# Main.net
KiCad netlist of a schematic drawn in Altium Designer
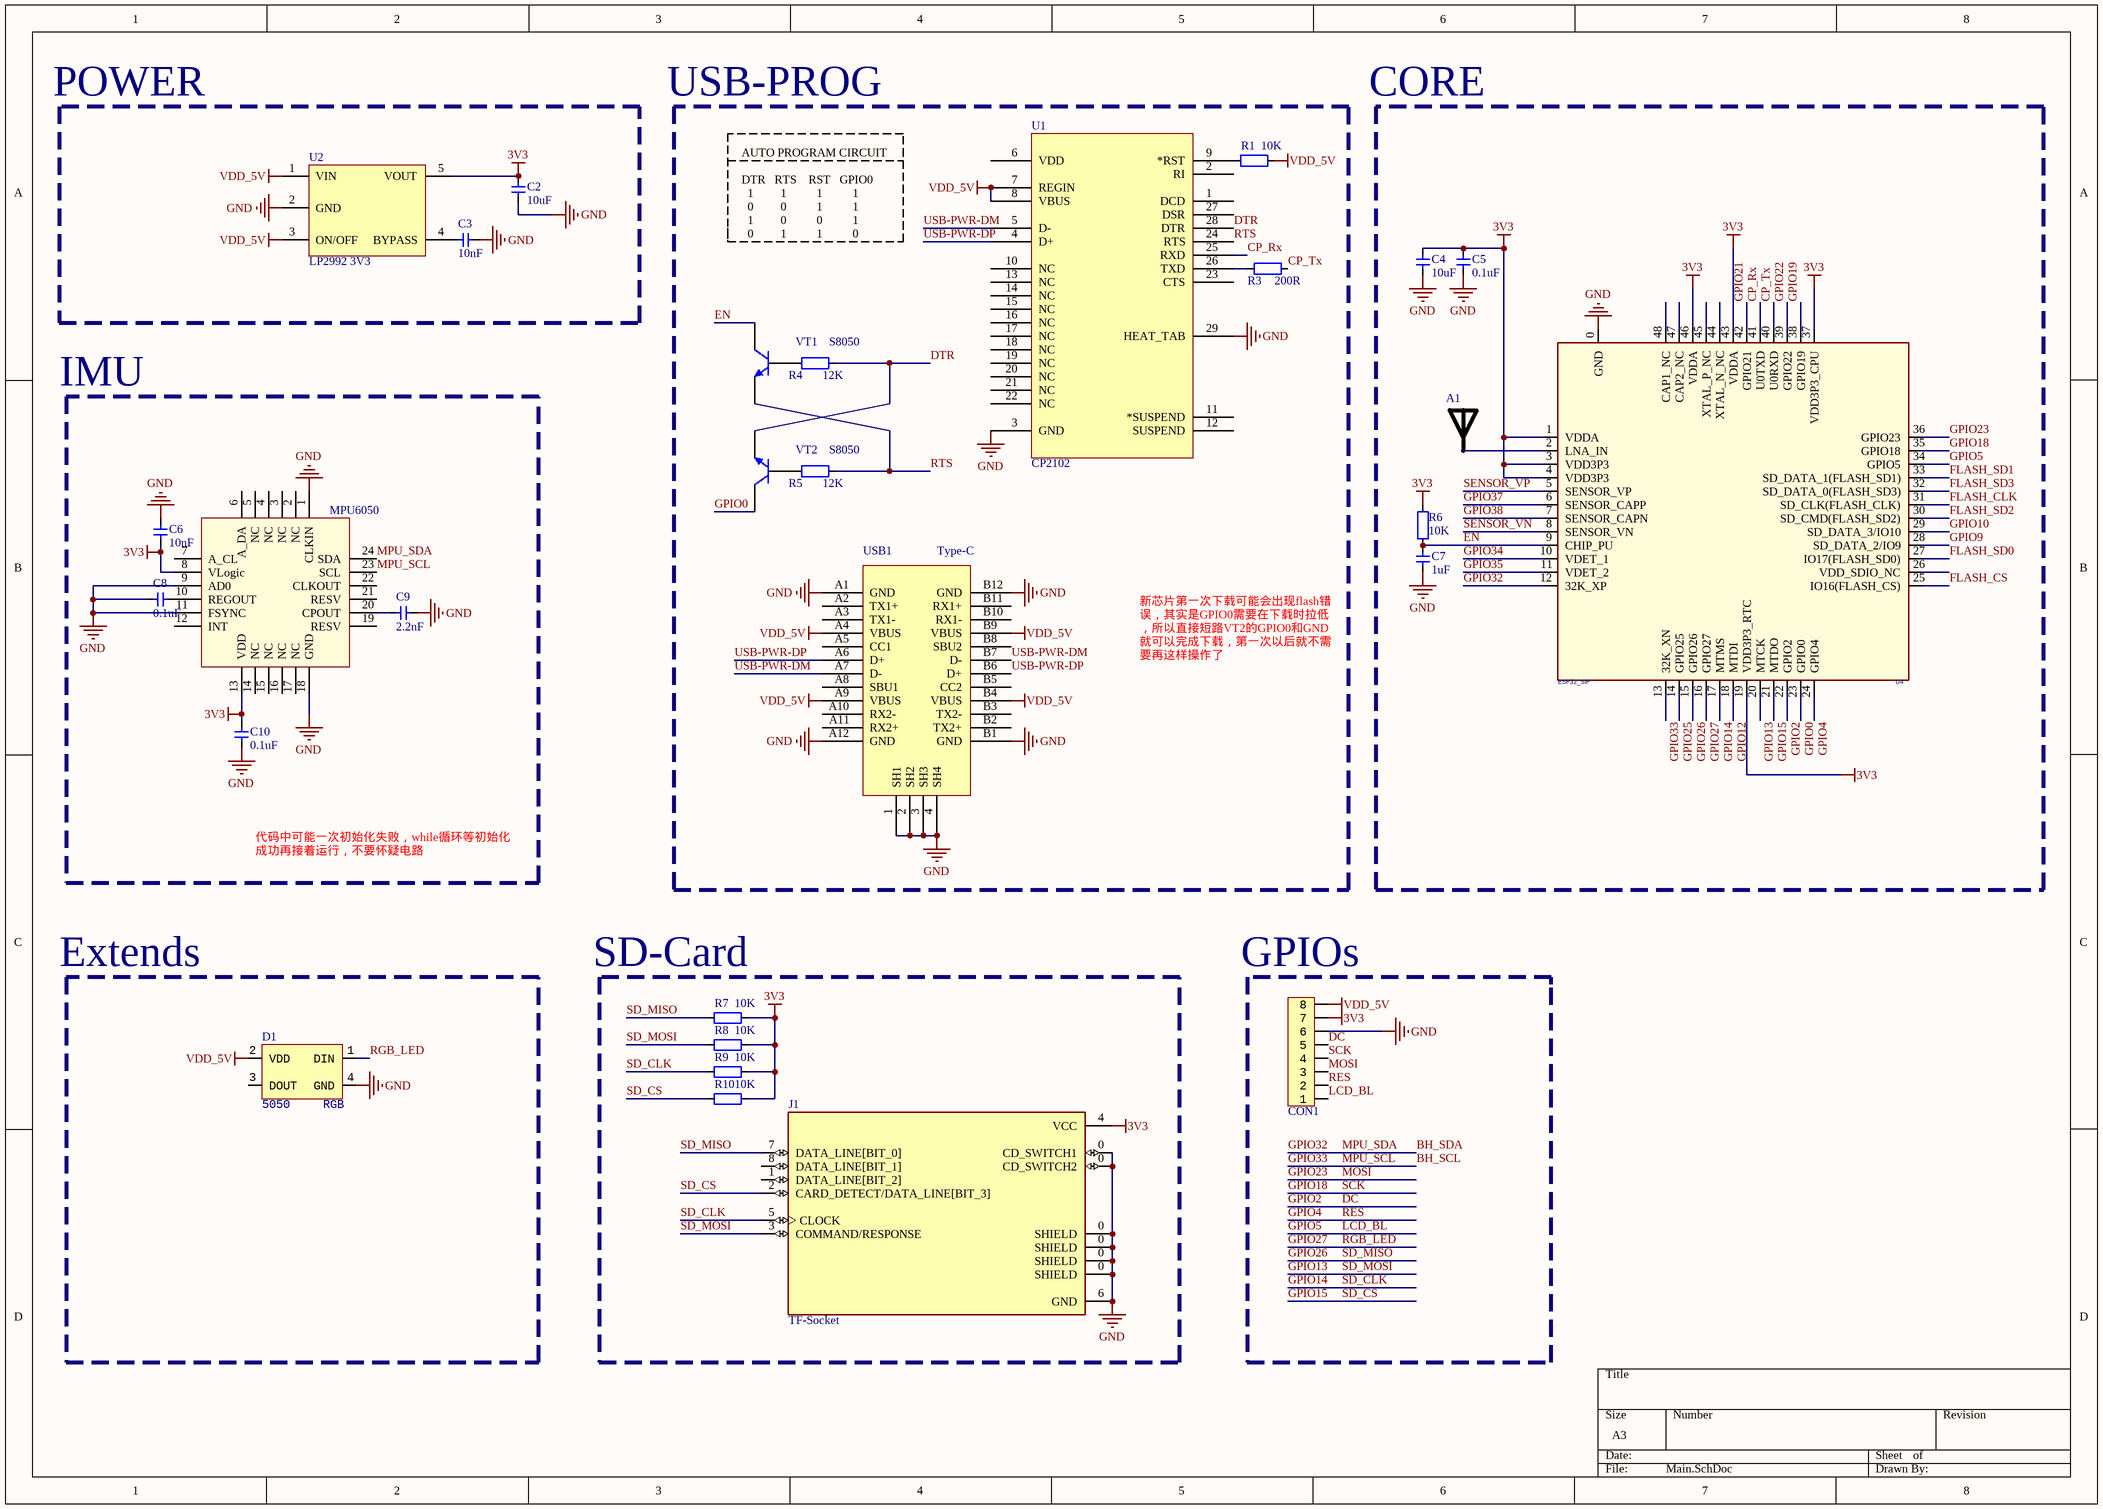
[diagram p0: Main.SchDoc]

(export (version "E")
  (design (tool "Eeschema 10.0.6"))
  (components
    (comp (ref "A1")
      (value "RAINSUN")
      (footprint "ANT-Rainsun-AN5120")
      (libsource (lib "MyPcbLib") (part "ANT-Rainsun-AP5120"))
    )
    (comp (ref "C2")
      (value "10uF")
      (footprint "CAP_0402")
      (description "Capacitor")
      (libsource (lib "MyPcbLib") (part "电容-0402"))
    )
    (comp (ref "C3")
      (value "10nF")
      (footprint "CAP_0402")
      (description "Capacitor")
      (libsource (lib "MyPcbLib") (part "电容-0402"))
    )
    (comp (ref "C4")
      (value "10uF")
      (footprint "CAP_0402")
      (description "Capacitor")
      (libsource (lib "MyPcbLib") (part "电容-0402"))
    )
    (comp (ref "C5")
      (value "0.1uF")
      (footprint "CAP_0402")
      (description "Capacitor")
      (libsource (lib "MyPcbLib") (part "电容-0402"))
    )
    (comp (ref "C6")
      (value "10nF")
      (footprint "CAP_0402")
      (description "Capacitor")
      (libsource (lib "MyPcbLib") (part "电容-0402"))
    )
    (comp (ref "C7")
      (value "1uF")
      (footprint "CAP_0402")
      (description "Capacitor")
      (libsource (lib "MyPcbLib") (part "电容-0402"))
    )
    (comp (ref "C8")
      (value "0.1uF")
      (footprint "CAP_0402")
      (description "Capacitor")
      (libsource (lib "MyPcbLib") (part "电容-0402"))
    )
    (comp (ref "C9")
      (value "2.2nF")
      (footprint "CAP_0402")
      (description "Capacitor")
      (libsource (lib "MyPcbLib") (part "电容-0402"))
    )
    (comp (ref "C10")
      (value "0.1uF")
      (footprint "CAP_0402")
      (description "Capacitor")
      (libsource (lib "MyPcbLib") (part "电容-0402"))
    )
    (comp (ref "CON1")
      (value "FFC_0.5_8")
      (footprint "FFC_0.5_8")
      (description "FFC")
      (libsource (lib "KitSprout") (part "FFC_0.5_8"))
    )
    (comp (ref "D1")
      (value "RGB")
      (footprint "LED_WS2812_CE")
      (description "LED")
      (fields (field (name "TYPE") "5050"))
      (libsource (lib "KitSprout") (part "LED_5050_WS2812B"))
    )
    (comp (ref "J1")
      (value "TF-Socket")
      (footprint "TF_F")
      (description "10 _8 + 2_ Position Card Connector Secure Digital - microSDâ„¢ Surface Mount, Right Angle Gold")
      (fields (field (name "MP") "1140084168") (field (name "MF") "Amphenol Commercial Products"))
      (libsource (lib "MyPcbLib") (part "TF-Socket"))
    )
    (comp (ref "R1")
      (value "10K")
      (footprint "RES_0402")
      (description "Resistor")
      (libsource (lib "MyPcbLib") (part "电阻-0402"))
    )
    (comp (ref "R3")
      (value "200R")
      (footprint "RES_0402")
      (description "Resistor")
      (libsource (lib "MyPcbLib") (part "电阻-0402"))
    )
    (comp (ref "R4")
      (value "12K")
      (footprint "RES_0402")
      (description "Resistor")
      (libsource (lib "MyPcbLib") (part "电阻-0402"))
    )
    (comp (ref "R5")
      (value "12K")
      (footprint "RES_0402")
      (description "Resistor")
      (libsource (lib "MyPcbLib") (part "电阻-0402"))
    )
    (comp (ref "R6")
      (value "10K")
      (footprint "RES_0402")
      (description "Resistor")
      (libsource (lib "") (part "电阻-0402_1"))
    )
    (comp (ref "R7")
      (value "10K")
      (footprint "RES_0402")
      (description "Resistor")
      (libsource (lib "MyPcbLib") (part "电阻-0402"))
    )
    (comp (ref "R8")
      (value "10K")
      (footprint "RES_0402")
      (description "Resistor")
      (libsource (lib "MyPcbLib") (part "电阻-0402"))
    )
    (comp (ref "R9")
      (value "10K")
      (footprint "RES_0402")
      (description "Resistor")
      (libsource (lib "MyPcbLib") (part "电阻-0402"))
    )
    (comp (ref "R10")
      (value "10K")
      (footprint "RES_0402")
      (description "Resistor")
      (libsource (lib "MyPcbLib") (part "电阻-0402"))
    )
    (comp (ref "U1")
      (value "CP2102")
      (footprint "QFN-28")
      (description "USB转TTL")
      (libsource (lib "mLib") (part "CP2102"))
    )
    (comp (ref "U2")
      (value "LP2992 3V3")
      (footprint "SOT23-5")
      (description "LDO")
      (libsource (lib "MyPcbLib") (part "LP2992"))
    )
    (comp (ref "U3")
      (value "MPU6050")
      (footprint "QFN-24")
      (description "六轴传感器")
      (libsource (lib "mLib") (part "MPU6050"))
    )
    (comp (ref "U4")
      (value "ESP32_SIP")
      (footprint "QFN-48_7X7")
      (libsource (lib "MyPcbLib") (part "ESP32-PICO"))
    )
    (comp (ref "USB1")
      (value "Type-C")
      (footprint "Type-C-TOP")
      (libsource (lib "MyPcbLib") (part "USB-Type-C-TOP"))
    )
    (comp (ref "VT1")
      (value "S8050")
      (footprint "SMT_TRIODE_NPN")
      (description "Surface mount NPN transistor, package SOT-23")
      (libsource (lib "MyPcbLib") (part "SMT_TRIODE_NPN"))
    )
    (comp (ref "VT2")
      (value "S8050")
      (footprint "SMT_TRIODE_NPN")
      (description "Surface mount NPN transistor, package SOT-23")
      (libsource (lib "MyPcbLib") (part "SMT_TRIODE_NPN"))
    )
  )
  (nets
    (net (code "1") (name "/BH_SCL") (class "Default")
      (node (ref "U3") (pin "23") (pinfunction "SCL_23") (pintype "passive"))
      (node (ref "U4") (pin "13") (pinfunction "32K_XN_13") (pintype "passive"))
    )
    (net (code "2") (name "/BH_SDA") (class "Default")
      (node (ref "U3") (pin "24") (pinfunction "SDA_24") (pintype "passive"))
      (node (ref "U4") (pin "12") (pinfunction "32K_XP_12") (pintype "passive"))
    )
    (net (code "3") (name "/CP_Rx") (class "Default")
      (node (ref "U1") (pin "25") (pinfunction "RXD_25") (pintype "passive"))
      (node (ref "U4") (pin "41") (pinfunction "U0TXD_41") (pintype "power_in"))
    )
    (net (code "4") (name "/CP_Tx") (class "Default")
      (node (ref "R3") (pin "1") (pinfunction "1_1") (pintype "passive"))
      (node (ref "U4") (pin "40") (pinfunction "U0RXD_40") (pintype "power_in"))
    )
    (net (code "5") (name "/DC") (class "Default")
      (node (ref "CON1") (pin "5") (pinfunction "5_5") (pintype "passive"))
      (node (ref "U4") (pin "22") (pinfunction "GPIO2_22") (pintype "passive"))
    )
    (net (code "6") (name "/DTR") (class "Default")
      (node (ref "R4") (pin "1") (pinfunction "1_1") (pintype "passive"))
      (node (ref "U1") (pin "28") (pinfunction "DTR_28") (pintype "passive"))
      (node (ref "VT2") (pin "2") (pinfunction "E_2") (pintype "passive"))
    )
    (net (code "7") (name "/EN") (class "Default")
      (node (ref "C7") (pin "1") (pinfunction "1_1") (pintype "passive"))
      (node (ref "R6") (pin "2") (pinfunction "2_2") (pintype "passive"))
      (node (ref "U4") (pin "9") (pinfunction "CHIP_PU_9") (pintype "passive"))
      (node (ref "VT1") (pin "3") (pinfunction "C_3") (pintype "passive"))
    )
    (net (code "8") (name "/FLASH_CLK") (class "Default")
      (node (ref "U4") (pin "31") (pinfunction "SD_CLK(FLASH_CLK)_31") (pintype "passive"))
    )
    (net (code "9") (name "/FLASH_CS") (class "Default")
      (node (ref "U4") (pin "25") (pinfunction "IO16(FLASH_CS)_25") (pintype "passive"))
    )
    (net (code "10") (name "/FLASH_SD0") (class "Default")
      (node (ref "U4") (pin "27") (pinfunction "IO17(FLASH_SD0)_27") (pintype "passive"))
    )
    (net (code "11") (name "/FLASH_SD1") (class "Default")
      (node (ref "U4") (pin "33") (pinfunction "SD_DATA_1(FLASH_SD1)_33") (pintype "passive"))
    )
    (net (code "12") (name "/FLASH_SD2") (class "Default")
      (node (ref "U4") (pin "30") (pinfunction "SD_CMD(FLASH_SD2)_30") (pintype "passive"))
    )
    (net (code "13") (name "/FLASH_SD3") (class "Default")
      (node (ref "U4") (pin "32") (pinfunction "SD_DATA_0(FLASH_SD3)_32") (pintype "passive"))
    )
    (net (code "14") (name "/GPIO0") (class "Default")
      (node (ref "U4") (pin "23") (pinfunction "GPIO0_23") (pintype "passive"))
      (node (ref "VT2") (pin "3") (pinfunction "C_3") (pintype "passive"))
    )
    (net (code "15") (name "/GPIO4") (class "Default")
      (node (ref "CON1") (pin "2") (pinfunction "2_2") (pintype "passive"))
      (node (ref "U4") (pin "24") (pinfunction "GPIO4_24") (pintype "passive"))
    )
    (net (code "16") (name "/GPIO5") (class "Default")
      (node (ref "CON1") (pin "1") (pinfunction "1_1") (pintype "passive"))
      (node (ref "U4") (pin "34") (pinfunction "GPIO5_34") (pintype "passive"))
    )
    (net (code "17") (name "/GPIO9") (class "Default")
      (node (ref "U4") (pin "28") (pinfunction "SD_DATA_2/IO9_28") (pintype "passive"))
    )
    (net (code "18") (name "/GPIO10") (class "Default")
      (node (ref "U4") (pin "29") (pinfunction "SD_DATA_3/IO10_29") (pintype "passive"))
    )
    (net (code "19") (name "/GPIO12") (class "Default")
      (node (ref "U4") (pin "18") (pinfunction "MTDI_18") (pintype "passive"))
    )
    (net (code "20") (name "/GPIO13") (class "Default")
      (node (ref "J1") (pin "3") (pinfunction "COMMAND/RESPONSE_3") (pintype "bidirectional"))
      (node (ref "R8") (pin "2") (pinfunction "2_2") (pintype "passive"))
      (node (ref "U4") (pin "20") (pinfunction "MTCK_20") (pintype "passive"))
    )
    (net (code "21") (name "/GPIO14") (class "Default")
      (node (ref "J1") (pin "5") (pinfunction "CLOCK_5") (pintype "bidirectional"))
      (node (ref "R9") (pin "2") (pinfunction "2_2") (pintype "passive"))
      (node (ref "U4") (pin "17") (pinfunction "MTMS_17") (pintype "passive"))
    )
    (net (code "22") (name "/GPIO15") (class "Default")
      (node (ref "J1") (pin "2") (pinfunction "CARD_DETECT/DATA_LINE[BIT_3]_2") (pintype "bidirectional"))
      (node (ref "R10") (pin "2") (pinfunction "2_2") (pintype "passive"))
      (node (ref "U4") (pin "21") (pinfunction "MTDO_21") (pintype "passive"))
    )
    (net (code "23") (name "/GPIO18") (class "Default")
      (node (ref "CON1") (pin "4") (pinfunction "4_4") (pintype "passive"))
      (node (ref "U4") (pin "35") (pinfunction "GPIO18_35") (pintype "passive"))
    )
    (net (code "24") (name "/GPIO19") (class "Default")
      (node (ref "U4") (pin "38") (pinfunction "GPIO19_38") (pintype "passive"))
    )
    (net (code "25") (name "/GPIO21") (class "Default")
      (node (ref "U4") (pin "42") (pinfunction "GPIO21_42") (pintype "passive"))
    )
    (net (code "26") (name "/GPIO22") (class "Default")
      (node (ref "U4") (pin "39") (pinfunction "GPIO22_39") (pintype "passive"))
    )
    (net (code "27") (name "/GPIO23") (class "Default")
      (node (ref "CON1") (pin "3") (pinfunction "3_3") (pintype "passive"))
      (node (ref "U4") (pin "36") (pinfunction "GPIO23_36") (pintype "passive"))
    )
    (net (code "28") (name "/GPIO25") (class "Default")
      (node (ref "U4") (pin "14") (pinfunction "GPIO25_14") (pintype "passive"))
    )
    (net (code "29") (name "/GPIO26") (class "Default")
      (node (ref "J1") (pin "7") (pinfunction "DATA_LINE[BIT_0]_7") (pintype "bidirectional"))
      (node (ref "R7") (pin "2") (pinfunction "2_2") (pintype "passive"))
      (node (ref "U4") (pin "15") (pinfunction "GPIO26_15") (pintype "passive"))
    )
    (net (code "30") (name "/GPIO27") (class "Default")
      (node (ref "D1") (pin "1") (pinfunction "DIN_1") (pintype "passive"))
      (node (ref "U4") (pin "16") (pinfunction "GPIO27_16") (pintype "passive"))
    )
    (net (code "31") (name "/GPIO34") (class "Default")
      (node (ref "U4") (pin "10") (pinfunction "VDET_1_10") (pintype "passive"))
    )
    (net (code "32") (name "/GPIO35") (class "Default")
      (node (ref "U4") (pin "11") (pinfunction "VDET_2_11") (pintype "passive"))
    )
    (net (code "33") (name "/GPIO37") (class "Default")
      (node (ref "U4") (pin "6") (pinfunction "SENSOR_CAPP_6") (pintype "passive"))
    )
    (net (code "34") (name "/GPIO38") (class "Default")
      (node (ref "U4") (pin "7") (pinfunction "SENSOR_CAPN_7") (pintype "passive"))
    )
    (net (code "35") (name "/RTS") (class "Default")
      (node (ref "R5") (pin "1") (pinfunction "1_1") (pintype "passive"))
      (node (ref "U1") (pin "24") (pinfunction "RTS_24") (pintype "passive"))
      (node (ref "VT1") (pin "2") (pinfunction "E_2") (pintype "passive"))
    )
    (net (code "36") (name "/SENSOR_VN") (class "Default")
      (node (ref "U4") (pin "8") (pinfunction "SENSOR_VN_8") (pintype "passive"))
    )
    (net (code "37") (name "/SENSOR_VP") (class "Default")
      (node (ref "U4") (pin "5") (pinfunction "SENSOR_VP_5") (pintype "passive"))
    )
    (net (code "38") (name "/USB-PWR-DM") (class "Default")
      (node (ref "U1") (pin "5") (pinfunction "D-_5") (pintype "passive"))
      (node (ref "USB1") (pin "A7") (pinfunction "D-_A7") (pintype "passive"))
      (node (ref "USB1") (pin "B7") (pinfunction "D-_B7") (pintype "passive"))
    )
    (net (code "39") (name "/USB-PWR-DP") (class "Default")
      (node (ref "U1") (pin "4") (pinfunction "D+_4") (pintype "passive"))
      (node (ref "USB1") (pin "A6") (pinfunction "D+_A6") (pintype "passive"))
      (node (ref "USB1") (pin "B6") (pinfunction "D+_B6") (pintype "passive"))
    )
    (net (code "40") (name "3V3") (class "Default")
      (node (ref "C10") (pin "2") (pinfunction "2_2") (pintype "passive"))
      (node (ref "C2") (pin "2") (pinfunction "2_2") (pintype "passive"))
      (node (ref "C4") (pin "2") (pinfunction "2_2") (pintype "passive"))
      (node (ref "C5") (pin "2") (pinfunction "2_2") (pintype "passive"))
      (node (ref "C6") (pin "1") (pinfunction "1_1") (pintype "passive"))
      (node (ref "CON1") (pin "7") (pinfunction "7_7") (pintype "passive"))
      (node (ref "J1") (pin "4") (pinfunction "VCC_4") (pintype "power_in"))
      (node (ref "R10") (pin "1") (pinfunction "1_1") (pintype "passive"))
      (node (ref "R6") (pin "1") (pinfunction "1_1") (pintype "passive"))
      (node (ref "R7") (pin "1") (pinfunction "1_1") (pintype "passive"))
      (node (ref "R8") (pin "1") (pinfunction "1_1") (pintype "passive"))
      (node (ref "R9") (pin "1") (pinfunction "1_1") (pintype "passive"))
      (node (ref "U2") (pin "5") (pinfunction "VOUT_5") (pintype "passive"))
      (node (ref "U3") (pin "13") (pinfunction "VDD_13") (pintype "passive"))
      (node (ref "U3") (pin "8") (pinfunction "VLogic_8") (pintype "passive"))
      (node (ref "U4") (pin "1") (pinfunction "VDDA_1") (pintype "power_in"))
      (node (ref "U4") (pin "19") (pinfunction "VDD3P3_RTC_19") (pintype "power_in"))
      (node (ref "U4") (pin "3") (pinfunction "VDD3P3_3") (pintype "power_in"))
      (node (ref "U4") (pin "37") (pinfunction "VDD3P3_CPU_37") (pintype "power_in"))
      (node (ref "U4") (pin "4") (pinfunction "VDD3P3_4") (pintype "power_in"))
      (node (ref "U4") (pin "43") (pinfunction "VDDA_43") (pintype "power_in"))
      (node (ref "U4") (pin "46") (pinfunction "VDDA_46") (pintype "power_in"))
    )
    (net (code "41") (name "GND") (class "Default")
      (node (ref "C10") (pin "1") (pinfunction "1_1") (pintype "passive"))
      (node (ref "C2") (pin "1") (pinfunction "1_1") (pintype "passive"))
      (node (ref "C3") (pin "1") (pinfunction "1_1") (pintype "passive"))
      (node (ref "C4") (pin "1") (pinfunction "1_1") (pintype "passive"))
      (node (ref "C5") (pin "1") (pinfunction "1_1") (pintype "passive"))
      (node (ref "C6") (pin "2") (pinfunction "2_2") (pintype "passive"))
      (node (ref "C7") (pin "2") (pinfunction "2_2") (pintype "passive"))
      (node (ref "C8") (pin "2") (pinfunction "2_2") (pintype "passive"))
      (node (ref "C9") (pin "1") (pinfunction "1_1") (pintype "passive"))
      (node (ref "CON1") (pin "6") (pinfunction "6_6") (pintype "passive"))
      (node (ref "D1") (pin "4") (pinfunction "GND_4") (pintype "passive"))
      (node (ref "J1") (pin "0") (pinfunction "SHIELD_0") (pintype "passive"))
      (node (ref "J1") (pin "6") (pinfunction "GND_6") (pintype "power_in"))
      (node (ref "U1") (pin "29") (pinfunction "HEAT_TAB_29") (pintype "passive"))
      (node (ref "U1") (pin "3") (pinfunction "GND_3") (pintype "passive"))
      (node (ref "U2") (pin "2") (pinfunction "GND_2") (pintype "passive"))
      (node (ref "U3") (pin "1") (pinfunction "CLKIN_1") (pintype "passive"))
      (node (ref "U3") (pin "11") (pinfunction "FSYNC_11") (pintype "passive"))
      (node (ref "U3") (pin "18") (pinfunction "GND_18") (pintype "passive"))
      (node (ref "U3") (pin "9") (pinfunction "AD0_9") (pintype "passive"))
      (node (ref "U4") (pin "0") (pinfunction "GND_0") (pintype "power_in"))
      (node (ref "USB1") (pin "1") (pinfunction "SH1_1") (pintype "passive"))
      (node (ref "USB1") (pin "2") (pinfunction "SH2_2") (pintype "passive"))
      (node (ref "USB1") (pin "3") (pinfunction "SH3_3") (pintype "passive"))
      (node (ref "USB1") (pin "4") (pinfunction "SH4_4") (pintype "passive"))
      (node (ref "USB1") (pin "A1") (pinfunction "GND_A1") (pintype "passive"))
      (node (ref "USB1") (pin "A12") (pinfunction "GND_A12") (pintype "passive"))
      (node (ref "USB1") (pin "B1") (pinfunction "GND_B1") (pintype "passive"))
      (node (ref "USB1") (pin "B12") (pinfunction "GND_B12") (pintype "passive"))
    )
    (net (code "42") (name "Net-(U1-*RST)") (class "Default")
      (node (ref "R1") (pin "2") (pinfunction "2_2") (pintype "passive"))
      (node (ref "U1") (pin "9") (pinfunction "*RST_9") (pintype "passive"))
    )
    (net (code "43") (name "Net-(U1-TXD)") (class "Default")
      (node (ref "R3") (pin "2") (pinfunction "2_2") (pintype "passive"))
      (node (ref "U1") (pin "26") (pinfunction "TXD_26") (pintype "passive"))
    )
    (net (code "44") (name "Net-(U2-BYPASS)") (class "Default")
      (node (ref "C3") (pin "2") (pinfunction "2_2") (pintype "passive"))
      (node (ref "U2") (pin "4") (pinfunction "BYPASS_4") (pintype "passive"))
    )
    (net (code "45") (name "Net-(U3-CPOUT)") (class "Default")
      (node (ref "C9") (pin "2") (pinfunction "2_2") (pintype "passive"))
      (node (ref "U3") (pin "20") (pinfunction "CPOUT_20") (pintype "passive"))
    )
    (net (code "46") (name "Net-(U3-REGOUT)") (class "Default")
      (node (ref "C8") (pin "1") (pinfunction "1_1") (pintype "passive"))
      (node (ref "U3") (pin "10") (pinfunction "REGOUT_10") (pintype "passive"))
    )
    (net (code "47") (name "Net-(U4-LNA_IN)") (class "Default")
      (node (ref "A1") (pin "1") (pinfunction "1_1") (pintype "passive"))
      (node (ref "U4") (pin "2") (pinfunction "LNA_IN_2") (pintype "passive"))
    )
    (net (code "48") (name "Net-(VT1-B)") (class "Default")
      (node (ref "R4") (pin "2") (pinfunction "2_2") (pintype "passive"))
      (node (ref "VT1") (pin "1") (pinfunction "B_1") (pintype "passive"))
    )
    (net (code "49") (name "Net-(VT2-B)") (class "Default")
      (node (ref "R5") (pin "2") (pinfunction "2_2") (pintype "passive"))
      (node (ref "VT2") (pin "1") (pinfunction "B_1") (pintype "passive"))
    )
    (net (code "50") (name "VDD_5V") (class "Default")
      (node (ref "CON1") (pin "8") (pinfunction "8_8") (pintype "passive"))
      (node (ref "D1") (pin "2") (pinfunction "VDD_2") (pintype "passive"))
      (node (ref "R1") (pin "1") (pinfunction "1_1") (pintype "passive"))
      (node (ref "U1") (pin "7") (pinfunction "REGIN_7") (pintype "passive"))
      (node (ref "U1") (pin "8") (pinfunction "VBUS_8") (pintype "passive"))
      (node (ref "U2") (pin "1") (pinfunction "VIN_1") (pintype "passive"))
      (node (ref "U2") (pin "3") (pinfunction "ON/OFF_3") (pintype "passive"))
      (node (ref "USB1") (pin "A4") (pinfunction "VBUS_A4") (pintype "passive"))
      (node (ref "USB1") (pin "A9") (pinfunction "VBUS_A9") (pintype "passive"))
      (node (ref "USB1") (pin "B4") (pinfunction "VBUS_B4") (pintype "passive"))
      (node (ref "USB1") (pin "B9") (pinfunction "VBUS_B9") (pintype "passive"))
    )
    (net (code "51") (name "unconnected-(D1-DOUT-Pad3)") (class "Default")
      (node (ref "D1") (pin "3") (pinfunction "DOUT_3") (pintype "passive"))
    )
    (net (code "52") (name "unconnected-(J1-DATA_LINE[BIT_1]-Pad8)") (class "Default")
      (node (ref "J1") (pin "8") (pinfunction "DATA_LINE[BIT_1]_8") (pintype "bidirectional"))
    )
    (net (code "53") (name "unconnected-(J1-DATA_LINE[BIT_2]-Pad1)") (class "Default")
      (node (ref "J1") (pin "1") (pinfunction "DATA_LINE[BIT_2]_1") (pintype "bidirectional"))
    )
    (net (code "54") (name "unconnected-(U1-*SUSPEND-Pad11)") (class "Default")
      (node (ref "U1") (pin "11") (pinfunction "*SUSPEND_11") (pintype "passive"))
    )
    (net (code "55") (name "unconnected-(U1-CTS-Pad23)") (class "Default")
      (node (ref "U1") (pin "23") (pinfunction "CTS_23") (pintype "passive"))
    )
    (net (code "56") (name "unconnected-(U1-DCD-Pad1)") (class "Default")
      (node (ref "U1") (pin "1") (pinfunction "DCD_1") (pintype "passive"))
    )
    (net (code "57") (name "unconnected-(U1-DSR-Pad27)") (class "Default")
      (node (ref "U1") (pin "27") (pinfunction "DSR_27") (pintype "passive"))
    )
    (net (code "58") (name "unconnected-(U1-NC-Pad10)") (class "Default")
      (node (ref "U1") (pin "10") (pinfunction "NC_10") (pintype "passive"))
    )
    (net (code "59") (name "unconnected-(U1-NC-Pad13)") (class "Default")
      (node (ref "U1") (pin "13") (pinfunction "NC_13") (pintype "passive"))
    )
    (net (code "60") (name "unconnected-(U1-NC-Pad14)") (class "Default")
      (node (ref "U1") (pin "14") (pinfunction "NC_14") (pintype "passive"))
    )
    (net (code "61") (name "unconnected-(U1-NC-Pad15)") (class "Default")
      (node (ref "U1") (pin "15") (pinfunction "NC_15") (pintype "passive"))
    )
    (net (code "62") (name "unconnected-(U1-NC-Pad16)") (class "Default")
      (node (ref "U1") (pin "16") (pinfunction "NC_16") (pintype "passive"))
    )
    (net (code "63") (name "unconnected-(U1-NC-Pad17)") (class "Default")
      (node (ref "U1") (pin "17") (pinfunction "NC_17") (pintype "passive"))
    )
    (net (code "64") (name "unconnected-(U1-NC-Pad18)") (class "Default")
      (node (ref "U1") (pin "18") (pinfunction "NC_18") (pintype "passive"))
    )
    (net (code "65") (name "unconnected-(U1-NC-Pad19)") (class "Default")
      (node (ref "U1") (pin "19") (pinfunction "NC_19") (pintype "passive"))
    )
    (net (code "66") (name "unconnected-(U1-NC-Pad20)") (class "Default")
      (node (ref "U1") (pin "20") (pinfunction "NC_20") (pintype "passive"))
    )
    (net (code "67") (name "unconnected-(U1-NC-Pad21)") (class "Default")
      (node (ref "U1") (pin "21") (pinfunction "NC_21") (pintype "passive"))
    )
    (net (code "68") (name "unconnected-(U1-NC-Pad22)") (class "Default")
      (node (ref "U1") (pin "22") (pinfunction "NC_22") (pintype "passive"))
    )
    (net (code "69") (name "unconnected-(U1-RI-Pad2)") (class "Default")
      (node (ref "U1") (pin "2") (pinfunction "RI_2") (pintype "passive"))
    )
    (net (code "70") (name "unconnected-(U1-SUSPEND-Pad12)") (class "Default")
      (node (ref "U1") (pin "12") (pinfunction "SUSPEND_12") (pintype "passive"))
    )
    (net (code "71") (name "unconnected-(U1-VDD-Pad6)") (class "Default")
      (node (ref "U1") (pin "6") (pinfunction "VDD_6") (pintype "passive"))
    )
    (net (code "72") (name "unconnected-(U3-A_CL-Pad7)") (class "Default")
      (node (ref "U3") (pin "7") (pinfunction "A_CL_7") (pintype "passive"))
    )
    (net (code "73") (name "unconnected-(U3-A_DA-Pad6)") (class "Default")
      (node (ref "U3") (pin "6") (pinfunction "A_DA_6") (pintype "passive"))
    )
    (net (code "74") (name "unconnected-(U3-CLKOUT-Pad22)") (class "Default")
      (node (ref "U3") (pin "22") (pinfunction "CLKOUT_22") (pintype "passive"))
    )
    (net (code "75") (name "unconnected-(U3-INT-Pad12)") (class "Default")
      (node (ref "U3") (pin "12") (pinfunction "INT_12") (pintype "passive"))
    )
    (net (code "76") (name "unconnected-(U3-NC-Pad2)") (class "Default")
      (node (ref "U3") (pin "2") (pinfunction "NC_2") (pintype "passive"))
    )
    (net (code "77") (name "unconnected-(U3-NC-Pad3)") (class "Default")
      (node (ref "U3") (pin "3") (pinfunction "NC_3") (pintype "passive"))
    )
    (net (code "78") (name "unconnected-(U3-NC-Pad4)") (class "Default")
      (node (ref "U3") (pin "4") (pinfunction "NC_4") (pintype "passive"))
    )
    (net (code "79") (name "unconnected-(U3-NC-Pad5)") (class "Default")
      (node (ref "U3") (pin "5") (pinfunction "NC_5") (pintype "passive"))
    )
    (net (code "80") (name "unconnected-(U3-NC-Pad14)") (class "Default")
      (node (ref "U3") (pin "14") (pinfunction "NC_14") (pintype "passive"))
    )
    (net (code "81") (name "unconnected-(U3-NC-Pad15)") (class "Default")
      (node (ref "U3") (pin "15") (pinfunction "NC_15") (pintype "passive"))
    )
    (net (code "82") (name "unconnected-(U3-NC-Pad16)") (class "Default")
      (node (ref "U3") (pin "16") (pinfunction "NC_16") (pintype "passive"))
    )
    (net (code "83") (name "unconnected-(U3-NC-Pad17)") (class "Default")
      (node (ref "U3") (pin "17") (pinfunction "NC_17") (pintype "passive"))
    )
    (net (code "84") (name "unconnected-(U3-RESV-Pad19)") (class "Default")
      (node (ref "U3") (pin "19") (pinfunction "RESV_19") (pintype "passive"))
    )
    (net (code "85") (name "unconnected-(U3-RESV-Pad21)") (class "Default")
      (node (ref "U3") (pin "21") (pinfunction "RESV_21") (pintype "passive"))
    )
    (net (code "86") (name "unconnected-(U4-CAP1_NC-Pad48)") (class "Default")
      (node (ref "U4") (pin "48") (pinfunction "CAP1_NC_48") (pintype "passive"))
    )
    (net (code "87") (name "unconnected-(U4-CAP2_NC-Pad47)") (class "Default")
      (node (ref "U4") (pin "47") (pinfunction "CAP2_NC_47") (pintype "passive"))
    )
    (net (code "88") (name "unconnected-(U4-VDD_SDIO_NC-Pad26)") (class "Default")
      (node (ref "U4") (pin "26") (pinfunction "VDD_SDIO_NC_26") (pintype "passive"))
    )
    (net (code "89") (name "unconnected-(U4-XTAL_N_NC-Pad44)") (class "Default")
      (node (ref "U4") (pin "44") (pinfunction "XTAL_N_NC_44") (pintype "passive"))
    )
    (net (code "90") (name "unconnected-(U4-XTAL_P_NC-Pad45)") (class "Default")
      (node (ref "U4") (pin "45") (pinfunction "XTAL_P_NC_45") (pintype "passive"))
    )
    (net (code "91") (name "unconnected-(USB1-CC1-PadA5)") (class "Default")
      (node (ref "USB1") (pin "A5") (pinfunction "CC1_A5") (pintype "passive"))
    )
    (net (code "92") (name "unconnected-(USB1-CC2-PadB5)") (class "Default")
      (node (ref "USB1") (pin "B5") (pinfunction "CC2_B5") (pintype "passive"))
    )
    (net (code "93") (name "unconnected-(USB1-RX1+-PadB11)") (class "Default")
      (node (ref "USB1") (pin "B11") (pinfunction "RX1+_B11") (pintype "passive"))
    )
    (net (code "94") (name "unconnected-(USB1-RX1--PadB10)") (class "Default")
      (node (ref "USB1") (pin "B10") (pinfunction "RX1-_B10") (pintype "passive"))
    )
    (net (code "95") (name "unconnected-(USB1-RX2+-PadA11)") (class "Default")
      (node (ref "USB1") (pin "A11") (pinfunction "RX2+_A11") (pintype "passive"))
    )
    (net (code "96") (name "unconnected-(USB1-RX2--PadA10)") (class "Default")
      (node (ref "USB1") (pin "A10") (pinfunction "RX2-_A10") (pintype "passive"))
    )
    (net (code "97") (name "unconnected-(USB1-SBU1-PadA8)") (class "Default")
      (node (ref "USB1") (pin "A8") (pinfunction "SBU1_A8") (pintype "passive"))
    )
    (net (code "98") (name "unconnected-(USB1-SBU2-PadB8)") (class "Default")
      (node (ref "USB1") (pin "B8") (pinfunction "SBU2_B8") (pintype "passive"))
    )
    (net (code "99") (name "unconnected-(USB1-TX1+-PadA2)") (class "Default")
      (node (ref "USB1") (pin "A2") (pinfunction "TX1+_A2") (pintype "passive"))
    )
    (net (code "100") (name "unconnected-(USB1-TX1--PadA3)") (class "Default")
      (node (ref "USB1") (pin "A3") (pinfunction "TX1-_A3") (pintype "passive"))
    )
    (net (code "101") (name "unconnected-(USB1-TX2+-PadB2)") (class "Default")
      (node (ref "USB1") (pin "B2") (pinfunction "TX2+_B2") (pintype "passive"))
    )
    (net (code "102") (name "unconnected-(USB1-TX2--PadB3)") (class "Default")
      (node (ref "USB1") (pin "B3") (pinfunction "TX2-_B3") (pintype "passive"))
    )
  )
)
